# Clock_management.net
KiCad netlist of a schematic drawn in Altium Designer
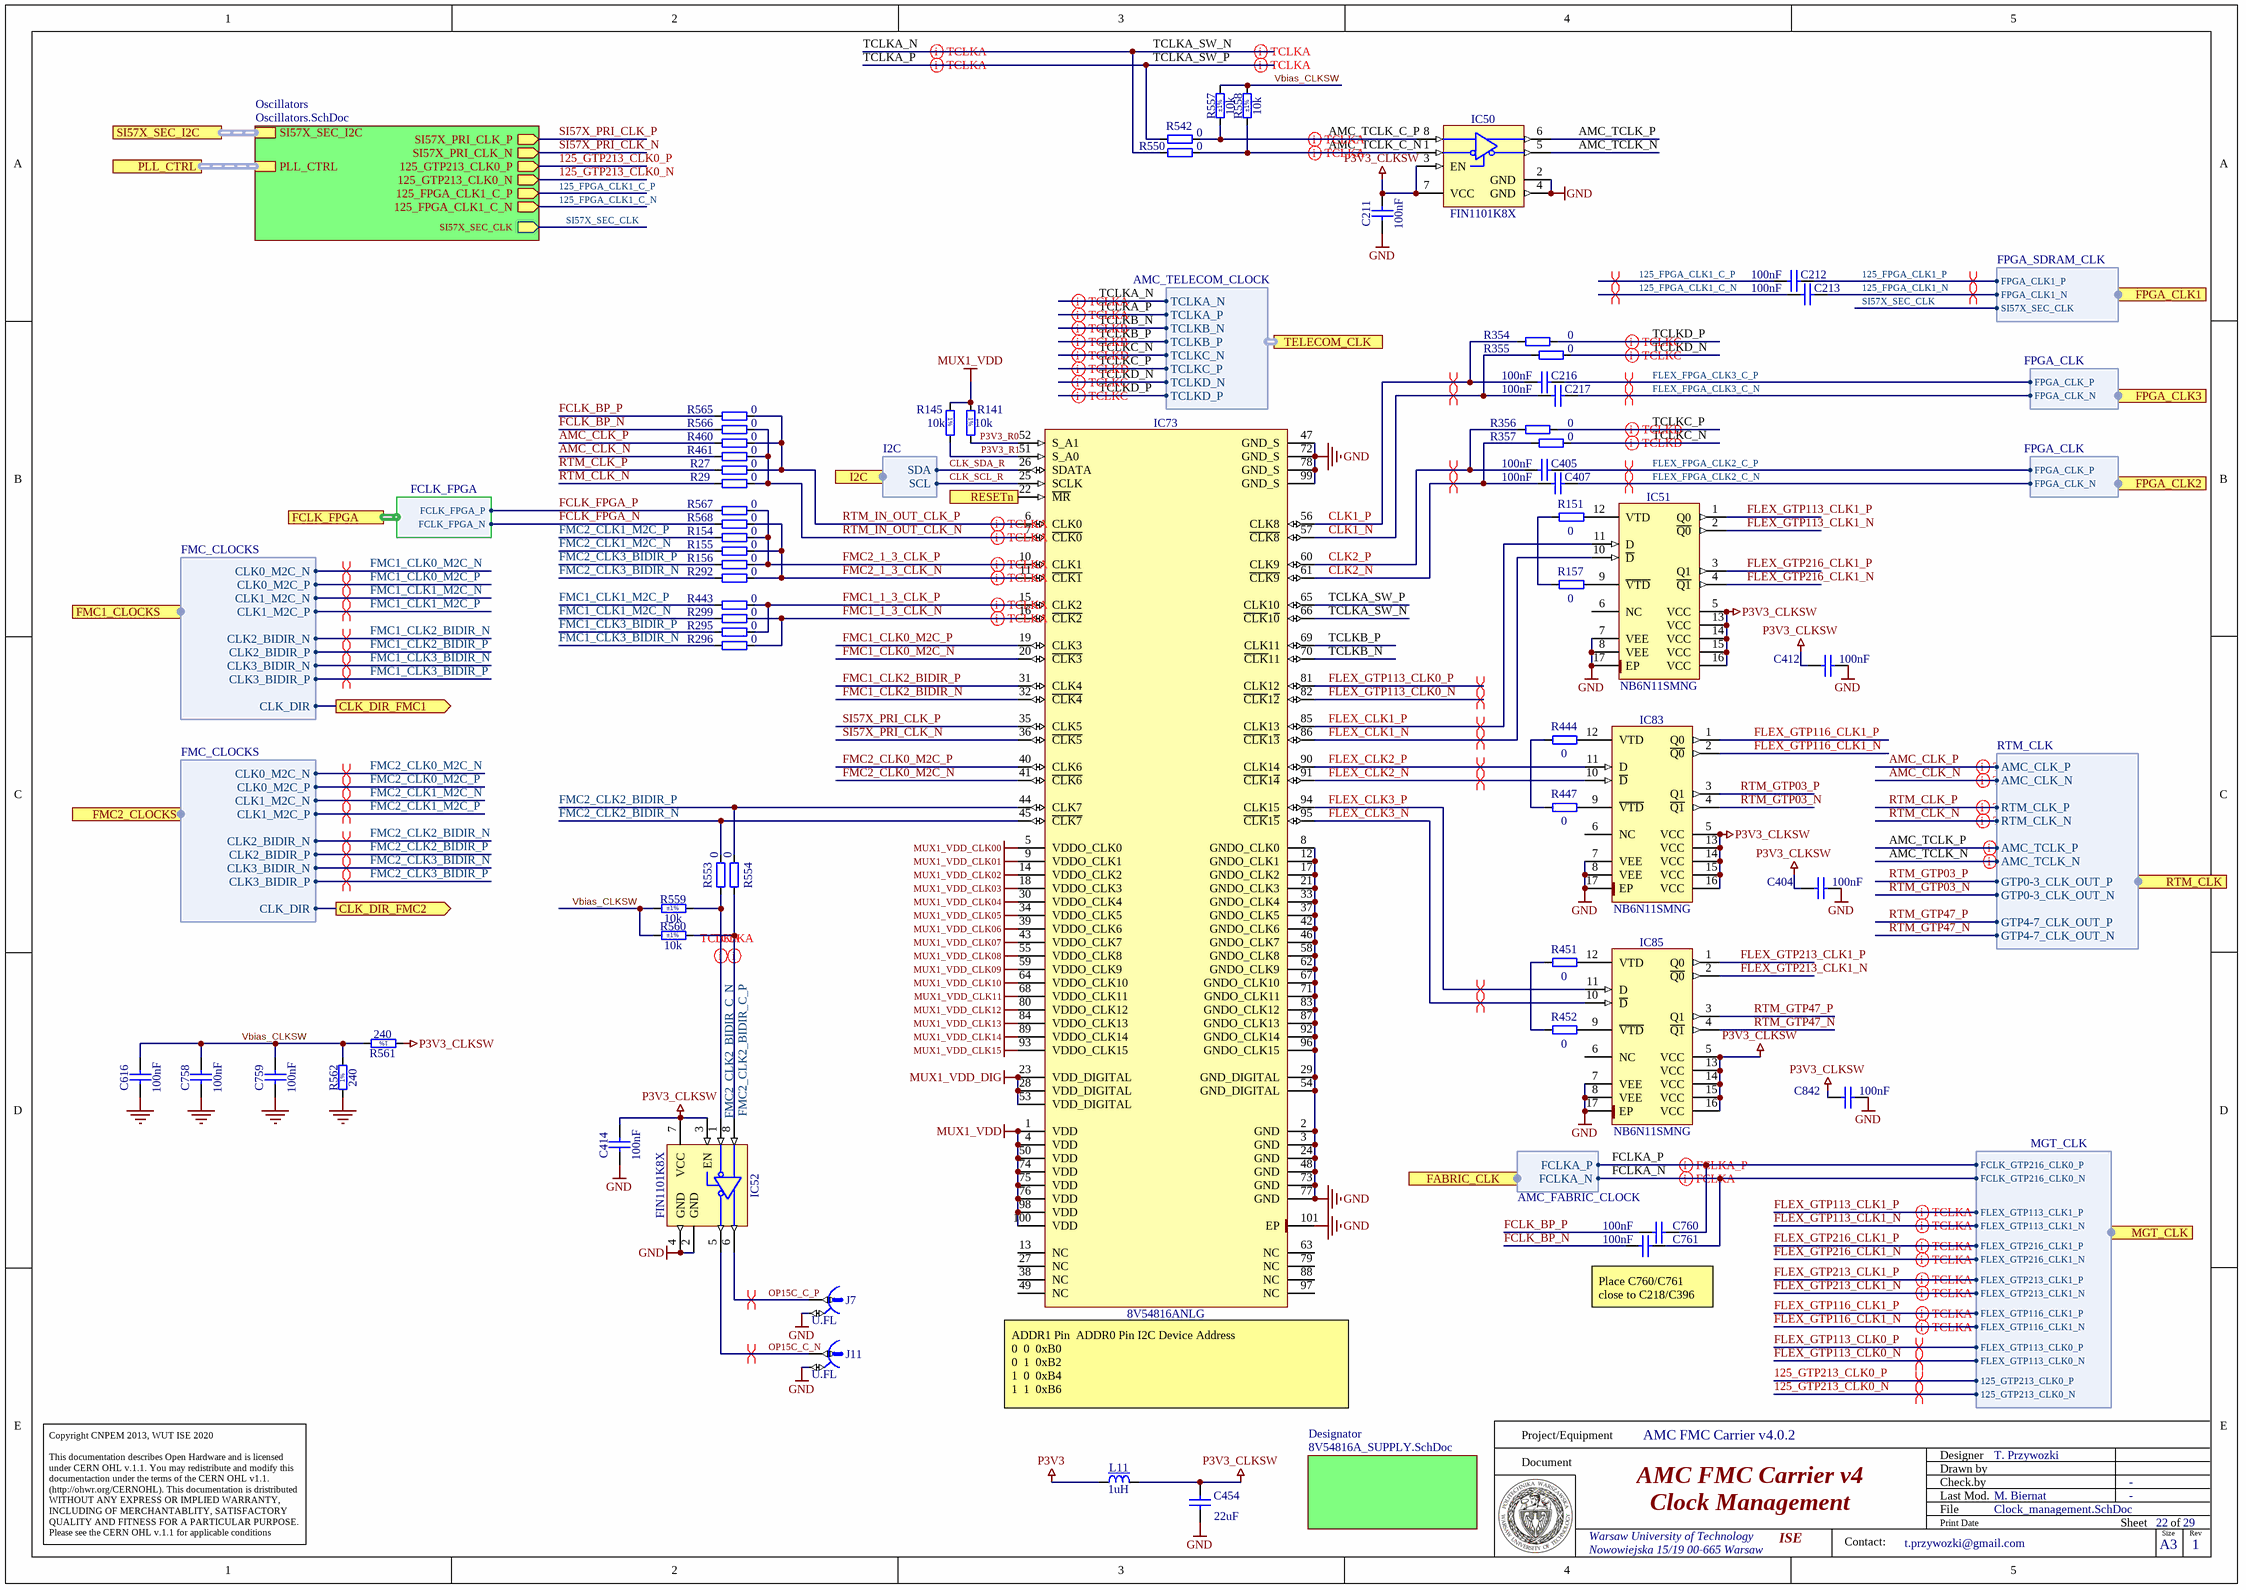
[diagram p0: Clock_management.SchDoc]

(export (version "E")
  (design (tool "Eeschema 10.0.6"))
  (components
    (comp (ref "C211")
      (value "100nF")
      (footprint "CAPC1005X55N")
      (description "Non-polarised capacitor")
      (fields
        (field (name "MANUFACTURER PART NUMBER") "CC0402_100NF_16V_10%_X5R")
        (field (name "MANUFACTURER") "GENERIC")
        (field (name "AUTHOR") "CERN DEM JLC")
      )
      (libsource (lib "Capacitors") (part "Capacitor - non polarized"))
    )
    (comp (ref "C212")
      (value "100nF")
      (footprint "CAPC0603X33N")
      (description "Non-polarised capacitor")
      (fields
        (field (name "PART NUMBER") "CC0201_100NF_6.3V_10%_X5R")
        (field (name "VOLTAGE") "6.3V")
        (field (name "AUTHOR") "CERN DEM JLC")
      )
      (libsource (lib "Capacitors") (part "Capacitor - non polarized"))
    )
    (comp (ref "C213")
      (value "100nF")
      (footprint "CAPC0603X33N")
      (description "Non-polarised capacitor")
      (fields
        (field (name "PART NUMBER") "CC0201_100NF_6.3V_10%_X5R")
        (field (name "VOLTAGE") "6.3V")
        (field (name "AUTHOR") "CERN DEM JLC")
      )
      (libsource (lib "Capacitors") (part "Capacitor - non polarized"))
    )
    (comp (ref "C216")
      (value "100nF")
      (footprint "CAPC0603X33N")
      (description "Non-polarised capacitor")
      (fields
        (field (name "PART NUMBER") "CC0201_100NF_6.3V_10%_X5R")
        (field (name "VOLTAGE") "6.3V")
        (field (name "AUTHOR") "CERN DEM JLC")
      )
      (libsource (lib "Capacitors") (part "Capacitor - non polarized"))
    )
    (comp (ref "C217")
      (value "100nF")
      (footprint "CAPC0603X33N")
      (description "Non-polarised capacitor")
      (fields
        (field (name "PART NUMBER") "CC0201_100NF_6.3V_10%_X5R")
        (field (name "VOLTAGE") "6.3V")
        (field (name "AUTHOR") "CERN DEM JLC")
      )
      (libsource (lib "Capacitors") (part "Capacitor - non polarized"))
    )
    (comp (ref "C404")
      (value "100nF")
      (footprint "CAPC0603X33N")
      (description "Non-polarised capacitor")
      (fields
        (field (name "PART NUMBER") "CC0201_100NF_6.3V_10%_X5R")
        (field (name "VOLTAGE") "6.3V")
        (field (name "AUTHOR") "CERN DEM JLC")
      )
      (libsource (lib "Capacitors") (part "Capacitor - non polarized"))
    )
    (comp (ref "C405")
      (value "100nF")
      (footprint "CAPC0603X33N")
      (description "Non-polarised capacitor")
      (fields
        (field (name "PART NUMBER") "CC0201_100NF_6.3V_10%_X5R")
        (field (name "VOLTAGE") "6.3V")
        (field (name "AUTHOR") "CERN DEM JLC")
      )
      (libsource (lib "Capacitors") (part "Capacitor - non polarized"))
    )
    (comp (ref "C407")
      (value "100nF")
      (footprint "CAPC0603X33N")
      (description "Non-polarised capacitor")
      (fields
        (field (name "PART NUMBER") "CC0201_100NF_6.3V_10%_X5R")
        (field (name "VOLTAGE") "6.3V")
        (field (name "AUTHOR") "CERN DEM JLC")
      )
      (libsource (lib "Capacitors") (part "Capacitor - non polarized"))
    )
    (comp (ref "C412")
      (value "100nF")
      (footprint "CAPC0603X33N")
      (description "Non-polarised capacitor")
      (fields
        (field (name "PART NUMBER") "CC0201_100NF_6.3V_10%_X5R")
        (field (name "VOLTAGE") "6.3V")
        (field (name "AUTHOR") "CERN DEM JLC")
      )
      (libsource (lib "Capacitors") (part "Capacitor - non polarized"))
    )
    (comp (ref "C414")
      (value "100nF")
      (footprint "CAPC1005X55N")
      (description "Non-polarised capacitor")
      (fields
        (field (name "MANUFACTURER PART NUMBER") "CC0402_100NF_16V_10%_X5R")
        (field (name "MANUFACTURER") "GENERIC")
        (field (name "AUTHOR") "CERN DEM JLC")
      )
      (libsource (lib "Capacitors") (part "Capacitor - non polarized"))
    )
    (comp (ref "C454")
      (value "22uF")
      (footprint "CAPC3216X180N")
      (description "Non-polarised capacitor")
      (fields
        (field (name "PART NUMBER") "CC1206_22UF_10V_10%_X7R")
        (field (name "VOLTAGE") "10V")
        (field (name "AUTHOR") "CERN DEM JLC")
      )
      (libsource (lib "Capacitors") (part "Capacitor - non polarized"))
    )
    (comp (ref "C616")
      (value "100nF")
      (footprint "CAPC1005X55N")
      (description "Non-polarised capacitor")
      (fields
        (field (name "MANUFACTURER PART NUMBER") "CC0402_100NF_16V_10%_X5R")
        (field (name "MANUFACTURER") "GENERIC")
        (field (name "AUTHOR") "CERN DEM JLC")
      )
      (libsource (lib "Capacitors") (part "Capacitor - non polarized"))
    )
    (comp (ref "C758")
      (value "100nF")
      (footprint "CAPC1005X55N")
      (description "Non-polarised capacitor")
      (fields
        (field (name "MANUFACTURER PART NUMBER") "CC0402_100NF_16V_10%_X5R")
        (field (name "MANUFACTURER") "GENERIC")
        (field (name "AUTHOR") "CERN DEM JLC")
      )
      (libsource (lib "Capacitors") (part "Capacitor - non polarized"))
    )
    (comp (ref "C759")
      (value "100nF")
      (footprint "CAPC1005X55N")
      (description "Non-polarised capacitor")
      (fields
        (field (name "MANUFACTURER PART NUMBER") "CC0402_100NF_16V_10%_X5R")
        (field (name "MANUFACTURER") "GENERIC")
        (field (name "AUTHOR") "CERN DEM JLC")
      )
      (libsource (lib "Capacitors") (part "Capacitor - non polarized"))
    )
    (comp (ref "C760")
      (value "100nF")
      (footprint "CAPC0603X33N")
      (description "Non-polarised capacitor")
      (fields
        (field (name "PART NUMBER") "CC0201_100NF_6.3V_10%_X5R")
        (field (name "VOLTAGE") "6.3V")
        (field (name "AUTHOR") "CERN DEM JLC")
      )
      (libsource (lib "Capacitors") (part "Capacitor - non polarized"))
    )
    (comp (ref "C761")
      (value "100nF")
      (footprint "CAPC0603X33N")
      (description "Non-polarised capacitor")
      (fields
        (field (name "PART NUMBER") "CC0201_100NF_6.3V_10%_X5R")
        (field (name "VOLTAGE") "6.3V")
        (field (name "AUTHOR") "CERN DEM JLC")
      )
      (libsource (lib "Capacitors") (part "Capacitor - non polarized"))
    )
    (comp (ref "C842")
      (value "100nF")
      (footprint "CAPC0603X33N")
      (description "Non-polarised capacitor")
      (fields
        (field (name "PART NUMBER") "CC0201_100NF_6.3V_10%_X5R")
        (field (name "VOLTAGE") "6.3V")
        (field (name "AUTHOR") "CERN DEM JLC")
      )
      (libsource (lib "Capacitors") (part "Capacitor - non polarized"))
    )
    (comp (ref "IC50")
      (value "FIN1101K8X")
      (footprint "SOP50P310X90-8N")
      (description "LVDS Single Port High Speed Repeater")
      (fields (field (name "MANUFACTURER") "FAIRCHILD SEMICONDUCTOR") (field (name "AUTHOR") "CERN DEM JLC"))
      (libsource (lib "") (part "FIN1101K8X_1"))
    )
    (comp (ref "IC51")
      (value "NB6N11SMNG")
      (footprint "QFN50P300X300X100-17N-S185")
      (description "3.3V 1:2 AnyLevel Input to LVDS Fanout Buffer / Translator")
      (fields (field (name "MANUFACTURER") "ON SEMICONDUCTOR") (field (name "AUTHOR") "CERN DEM JLC"))
      (libsource (lib "ICs And Semiconductors") (part "NB6N11SMN"))
    )
    (comp (ref "IC52")
      (value "FIN1101K8X")
      (footprint "SOP50P310X90-8N")
      (description "LVDS Single Port High Speed Repeater")
      (fields (field (name "MANUFACTURER") "FAIRCHILD SEMICONDUCTOR") (field (name "AUTHOR") "CERN DEM JLC"))
      (libsource (lib "ICs And Semiconductors") (part "FIN1101K8X"))
    )
    (comp (ref "IC73")
      (value "8V54816ANLG")
      (footprint "QFN40P1200X1200X90-101N-S690")
      (description "16-Port, Bi-directional M-LVDS Clock Cross-Point Switch")
      (fields
        (field (name "MANUFACTURER") "INTEGRATED DEVICE TECHNOLOGY (IDT)")
        (field (name "AUTHOR") "CERN DEM MR")
      )
      (libsource (lib "ICs And Semiconductors") (part "8V54816ANLG"))
    )
    (comp (ref "IC83")
      (value "NB6N11SMNG")
      (footprint "QFN50P300X300X100-17N-S185")
      (description "3.3V 1:2 AnyLevel Input to LVDS Fanout Buffer / Translator")
      (fields (field (name "MANUFACTURER") "ON SEMICONDUCTOR") (field (name "AUTHOR") "CERN DEM JLC"))
      (libsource (lib "ICs And Semiconductors") (part "NB6N11SMN"))
    )
    (comp (ref "IC85")
      (value "NB6N11SMNG")
      (footprint "QFN50P300X300X100-17N-S185")
      (description "3.3V 1:2 AnyLevel Input to LVDS Fanout Buffer / Translator")
      (fields (field (name "MANUFACTURER") "ON SEMICONDUCTOR") (field (name "AUTHOR") "CERN DEM JLC"))
      (libsource (lib "ICs And Semiconductors") (part "NB6N11SMN"))
    )
    (comp (ref "J7")
      (value "U.FL")
      (footprint "HIROSE_U.FL-R-SMT-1(10)")
      (fields
        (field (name "PART NUMBER") "HIROSE_U.FL-R-SMT-1(10)")
        (field (name "MANUFACTURER") "HIROSE (HRS)")
        (field (name "MANUFACTURER PART NUMBER") "U.FL-R-SMT-1(10)")
        (field (name "AUTHOR") "CERN DEM JLC")
      )
      (libsource (lib "Connectors") (part "Coax_1Male_1Shield"))
    )
    (comp (ref "J11")
      (value "U.FL")
      (footprint "HIROSE_U.FL-R-SMT-1(10)")
      (fields
        (field (name "PART NUMBER") "HIROSE_U.FL-R-SMT-1(10)")
        (field (name "MANUFACTURER") "HIROSE (HRS)")
        (field (name "MANUFACTURER PART NUMBER") "U.FL-R-SMT-1(10)")
        (field (name "AUTHOR") "CERN DEM JLC")
      )
      (libsource (lib "Connectors") (part "Coax_1Male_1Shield"))
    )
    (comp (ref "L11")
      (value "1uH")
      (footprint "IND_PANASONIC_ELLVGG")
      (description "Inductor With Core")
      (fields
        (field (name "PART NUMBER") "IND_1UH_30%_PANASONIC_ELLVGG1R0N")
        (field (name "POWER") "1.8A")
        (field (name "AUTHOR") "CERN DEM JLC")
      )
      (libsource (lib "Inductors & Transformers") (part "Inductor With Magnetic core"))
    )
    (comp (ref "R27")
      (value "0")
      (footprint "RESC1005X40N")
      (description "Resistor")
      (fields
        (field (name "PART NUMBER") "R0402_0R_JUMPER")
        (field (name "MANUFACTURER") "GENERIC")
        (field (name "AUTHOR") "CERN DEM JLC")
      )
      (libsource (lib "Resistors") (part "Resistor"))
    )
    (comp (ref "R29")
      (value "0")
      (footprint "RESC1005X40N")
      (description "Resistor")
      (fields
        (field (name "PART NUMBER") "R0402_0R_JUMPER")
        (field (name "MANUFACTURER") "GENERIC")
        (field (name "AUTHOR") "CERN DEM JLC")
      )
      (libsource (lib "Resistors") (part "Resistor"))
    )
    (comp (ref "R141")
      (value "10k")
      (footprint "RESC1005X40N")
      (description "Resistor - 1%")
      (fields
        (field (name "PART NUMBER") "R0402_10K_1%_0.0625W_100PPM")
        (field (name "POWER") "0.0625W")
        (field (name "AUTHOR") "CERN DEM JLC")
      )
      (libsource (lib "Resistors") (part "Resistor - 1%"))
    )
    (comp (ref "R145")
      (value "10k")
      (footprint "RESC1005X40N")
      (description "Resistor - 1%")
      (fields
        (field (name "PART NUMBER") "R0402_10K_1%_0.0625W_100PPM")
        (field (name "POWER") "0.0625W")
        (field (name "AUTHOR") "CERN DEM JLC")
      )
      (libsource (lib "Resistors") (part "Resistor - 1%"))
    )
    (comp (ref "R151")
      (value "0")
      (footprint "RESC1005X40N")
      (description "Resistor")
      (fields
        (field (name "PART NUMBER") "R0402_0R_JUMPER")
        (field (name "MANUFACTURER") "GENERIC")
        (field (name "AUTHOR") "CERN DEM JLC")
      )
      (libsource (lib "Resistors") (part "Resistor"))
    )
    (comp (ref "R154")
      (value "0")
      (footprint "RESC1005X40N")
      (description "Resistor")
      (fields
        (field (name "PART NUMBER") "R0402_0R_JUMPER")
        (field (name "MANUFACTURER") "GENERIC")
        (field (name "AUTHOR") "CERN DEM JLC")
      )
      (libsource (lib "Resistors") (part "Resistor"))
    )
    (comp (ref "R155")
      (value "0")
      (footprint "RESC1005X40N")
      (description "Resistor")
      (fields
        (field (name "PART NUMBER") "R0402_0R_JUMPER")
        (field (name "MANUFACTURER") "GENERIC")
        (field (name "AUTHOR") "CERN DEM JLC")
      )
      (libsource (lib "Resistors") (part "Resistor"))
    )
    (comp (ref "R156")
      (value "0")
      (footprint "RESC1005X40N")
      (description "Resistor")
      (fields
        (field (name "PART NUMBER") "R0402_0R_JUMPER")
        (field (name "MANUFACTURER") "GENERIC")
        (field (name "AUTHOR") "CERN DEM JLC")
      )
      (libsource (lib "Resistors") (part "Resistor"))
    )
    (comp (ref "R157")
      (value "0")
      (footprint "RESC1005X40N")
      (description "Resistor")
      (fields
        (field (name "PART NUMBER") "R0402_0R_JUMPER")
        (field (name "MANUFACTURER") "GENERIC")
        (field (name "AUTHOR") "CERN DEM JLC")
      )
      (libsource (lib "Resistors") (part "Resistor"))
    )
    (comp (ref "R292")
      (value "0")
      (footprint "RESC1005X40N")
      (description "Resistor")
      (fields
        (field (name "PART NUMBER") "R0402_0R_JUMPER")
        (field (name "MANUFACTURER") "GENERIC")
        (field (name "AUTHOR") "CERN DEM JLC")
      )
      (libsource (lib "Resistors") (part "Resistor"))
    )
    (comp (ref "R295")
      (value "0")
      (footprint "RESC1005X40N")
      (description "Resistor")
      (fields
        (field (name "PART NUMBER") "R0402_0R_JUMPER")
        (field (name "MANUFACTURER") "GENERIC")
        (field (name "AUTHOR") "CERN DEM JLC")
      )
      (libsource (lib "Resistors") (part "Resistor"))
    )
    (comp (ref "R296")
      (value "0")
      (footprint "RESC1005X40N")
      (description "Resistor")
      (fields
        (field (name "PART NUMBER") "R0402_0R_JUMPER")
        (field (name "MANUFACTURER") "GENERIC")
        (field (name "AUTHOR") "CERN DEM JLC")
      )
      (libsource (lib "Resistors") (part "Resistor"))
    )
    (comp (ref "R299")
      (value "0")
      (footprint "RESC1005X40N")
      (description "Resistor")
      (fields
        (field (name "PART NUMBER") "R0402_0R_JUMPER")
        (field (name "MANUFACTURER") "GENERIC")
        (field (name "AUTHOR") "CERN DEM JLC")
      )
      (libsource (lib "Resistors") (part "Resistor"))
    )
    (comp (ref "R354")
      (value "0")
      (footprint "RESC0603X28N")
      (description "Resistor")
      (fields
        (field (name "PART NUMBER") "R0201_0R_JUMPER")
        (field (name "MANUFACTURER") "GENERIC")
        (field (name "AUTHOR") "CERN DEM JLC")
      )
      (libsource (lib "Resistors") (part "Resistor"))
    )
    (comp (ref "R355")
      (value "0")
      (footprint "RESC0603X28N")
      (description "Resistor")
      (fields
        (field (name "PART NUMBER") "R0201_0R_JUMPER")
        (field (name "MANUFACTURER") "GENERIC")
        (field (name "AUTHOR") "CERN DEM JLC")
      )
      (libsource (lib "Resistors") (part "Resistor"))
    )
    (comp (ref "R356")
      (value "0")
      (footprint "RESC0603X28N")
      (description "Resistor")
      (fields
        (field (name "PART NUMBER") "R0201_0R_JUMPER")
        (field (name "MANUFACTURER") "GENERIC")
        (field (name "AUTHOR") "CERN DEM JLC")
      )
      (libsource (lib "Resistors") (part "Resistor"))
    )
    (comp (ref "R357")
      (value "0")
      (footprint "RESC0603X28N")
      (description "Resistor")
      (fields
        (field (name "PART NUMBER") "R0201_0R_JUMPER")
        (field (name "MANUFACTURER") "GENERIC")
        (field (name "AUTHOR") "CERN DEM JLC")
      )
      (libsource (lib "Resistors") (part "Resistor"))
    )
    (comp (ref "R443")
      (value "0")
      (footprint "RESC1005X40N")
      (description "Resistor")
      (fields
        (field (name "PART NUMBER") "R0402_0R_JUMPER")
        (field (name "MANUFACTURER") "GENERIC")
        (field (name "AUTHOR") "CERN DEM JLC")
      )
      (libsource (lib "Resistors") (part "Resistor"))
    )
    (comp (ref "R444")
      (value "0")
      (footprint "RESC1005X40N")
      (description "Resistor")
      (fields
        (field (name "PART NUMBER") "R0402_0R_JUMPER")
        (field (name "MANUFACTURER") "GENERIC")
        (field (name "AUTHOR") "CERN DEM JLC")
      )
      (libsource (lib "Resistors") (part "Resistor"))
    )
    (comp (ref "R447")
      (value "0")
      (footprint "RESC1005X40N")
      (description "Resistor")
      (fields
        (field (name "PART NUMBER") "R0402_0R_JUMPER")
        (field (name "MANUFACTURER") "GENERIC")
        (field (name "AUTHOR") "CERN DEM JLC")
      )
      (libsource (lib "Resistors") (part "Resistor"))
    )
    (comp (ref "R451")
      (value "0")
      (footprint "RESC1005X40N")
      (description "Resistor")
      (fields
        (field (name "PART NUMBER") "R0402_0R_JUMPER")
        (field (name "MANUFACTURER") "GENERIC")
        (field (name "AUTHOR") "CERN DEM JLC")
      )
      (libsource (lib "Resistors") (part "Resistor"))
    )
    (comp (ref "R452")
      (value "0")
      (footprint "RESC1005X40N")
      (description "Resistor")
      (fields
        (field (name "PART NUMBER") "R0402_0R_JUMPER")
        (field (name "MANUFACTURER") "GENERIC")
        (field (name "AUTHOR") "CERN DEM JLC")
      )
      (libsource (lib "Resistors") (part "Resistor"))
    )
    (comp (ref "R460")
      (value "0")
      (footprint "RESC1005X40N")
      (description "Resistor")
      (fields
        (field (name "PART NUMBER") "R0402_0R_JUMPER")
        (field (name "MANUFACTURER") "GENERIC")
        (field (name "AUTHOR") "CERN DEM JLC")
      )
      (libsource (lib "Resistors") (part "Resistor"))
    )
    (comp (ref "R461")
      (value "0")
      (footprint "RESC1005X40N")
      (description "Resistor")
      (fields
        (field (name "PART NUMBER") "R0402_0R_JUMPER")
        (field (name "MANUFACTURER") "GENERIC")
        (field (name "AUTHOR") "CERN DEM JLC")
      )
      (libsource (lib "Resistors") (part "Resistor"))
    )
    (comp (ref "R542")
      (value "0")
      (footprint "RESC1005X40N")
      (description "Resistor")
      (fields
        (field (name "PART NUMBER") "R0402_0R_JUMPER")
        (field (name "MANUFACTURER") "GENERIC")
        (field (name "AUTHOR") "CERN DEM JLC")
      )
      (libsource (lib "Resistors") (part "Resistor"))
    )
    (comp (ref "R550")
      (value "0")
      (footprint "RESC1005X40N")
      (description "Resistor")
      (fields
        (field (name "PART NUMBER") "R0402_0R_JUMPER")
        (field (name "MANUFACTURER") "GENERIC")
        (field (name "AUTHOR") "CERN DEM JLC")
      )
      (libsource (lib "Resistors") (part "Resistor"))
    )
    (comp (ref "R553")
      (value "0")
      (footprint "RESC1005X40N")
      (description "Resistor")
      (fields
        (field (name "PART NUMBER") "R0402_0R_JUMPER")
        (field (name "MANUFACTURER") "GENERIC")
        (field (name "AUTHOR") "CERN DEM JLC")
      )
      (libsource (lib "Resistors") (part "Resistor"))
    )
    (comp (ref "R554")
      (value "0")
      (footprint "RESC1005X40N")
      (description "Resistor")
      (fields
        (field (name "PART NUMBER") "R0402_0R_JUMPER")
        (field (name "MANUFACTURER") "GENERIC")
        (field (name "AUTHOR") "CERN DEM JLC")
      )
      (libsource (lib "Resistors") (part "Resistor"))
    )
    (comp (ref "R557")
      (value "10k")
      (footprint "RESC1005X40N")
      (description "Resistor - 1%")
      (fields
        (field (name "TOLERANCE") "±1%")
        (field (name "PART NUMBER") "R0402_10K_1%_0.0625W_100PPM")
        (field (name "POWER") "0.0625W")
        (field (name "AUTHOR") "CERN DEM JLC")
      )
      (libsource (lib "Resistors") (part "Resistor - 1%"))
    )
    (comp (ref "R558")
      (value "10k")
      (footprint "RESC1005X40N")
      (description "Resistor - 1%")
      (fields
        (field (name "TOLERANCE") "±1%")
        (field (name "PART NUMBER") "R0402_10K_1%_0.0625W_100PPM")
        (field (name "POWER") "0.0625W")
        (field (name "AUTHOR") "CERN DEM JLC")
      )
      (libsource (lib "Resistors") (part "Resistor - 1%"))
    )
    (comp (ref "R559")
      (value "10k")
      (footprint "RESC1005X40N")
      (description "Resistor - 1%")
      (fields
        (field (name "TOLERANCE") "±1%")
        (field (name "PART NUMBER") "R0402_10K_1%_0.0625W_100PPM")
        (field (name "POWER") "0.0625W")
        (field (name "AUTHOR") "CERN DEM JLC")
      )
      (libsource (lib "Resistors") (part "Resistor - 1%"))
    )
    (comp (ref "R560")
      (value "10k")
      (footprint "RESC1005X40N")
      (description "Resistor - 1%")
      (fields
        (field (name "TOLERANCE") "±1%")
        (field (name "PART NUMBER") "R0402_10K_1%_0.0625W_100PPM")
        (field (name "POWER") "0.0625W")
        (field (name "AUTHOR") "CERN DEM JLC")
      )
      (libsource (lib "Resistors") (part "Resistor - 1%"))
    )
    (comp (ref "R561")
      (value "240")
      (footprint "RESC1005X40N")
      (description "Resistor - 1%")
      (fields
        (field (name "MANUFACTURER PART NUMBER") "R0402_240R_1%_0.0625W_100PPM")
        (field (name "MANUFACTURER") "GENERIC")
        (field (name "AUTHOR") "CERN DEM JLC")
      )
      (libsource (lib "Resistors") (part "Resistor - 1%"))
    )
    (comp (ref "R562")
      (value "240")
      (footprint "RESC1005X40N")
      (description "Resistor - 1%")
      (fields
        (field (name "MANUFACTURER PART NUMBER") "R0402_240R_1%_0.0625W_100PPM")
        (field (name "MANUFACTURER") "GENERIC")
        (field (name "AUTHOR") "CERN DEM JLC")
      )
      (libsource (lib "Resistors") (part "Resistor - 1%"))
    )
    (comp (ref "R565")
      (value "0")
      (footprint "RESC1005X40N")
      (description "Resistor")
      (fields
        (field (name "PART NUMBER") "R0402_0R_JUMPER")
        (field (name "MANUFACTURER") "GENERIC")
        (field (name "AUTHOR") "CERN DEM JLC")
      )
      (libsource (lib "Resistors") (part "Resistor"))
    )
    (comp (ref "R566")
      (value "0")
      (footprint "RESC1005X40N")
      (description "Resistor")
      (fields
        (field (name "PART NUMBER") "R0402_0R_JUMPER")
        (field (name "MANUFACTURER") "GENERIC")
        (field (name "AUTHOR") "CERN DEM JLC")
      )
      (libsource (lib "Resistors") (part "Resistor"))
    )
    (comp (ref "R567")
      (value "0")
      (footprint "RESC1005X40N")
      (description "Resistor")
      (fields
        (field (name "PART NUMBER") "R0402_0R_JUMPER")
        (field (name "MANUFACTURER") "GENERIC")
        (field (name "AUTHOR") "CERN DEM JLC")
      )
      (libsource (lib "Resistors") (part "Resistor"))
    )
    (comp (ref "R568")
      (value "0")
      (footprint "RESC1005X40N")
      (description "Resistor")
      (fields
        (field (name "PART NUMBER") "R0402_0R_JUMPER")
        (field (name "MANUFACTURER") "GENERIC")
        (field (name "AUTHOR") "CERN DEM JLC")
      )
      (libsource (lib "Resistors") (part "Resistor"))
    )
  )
  (nets
    (net (code "12") (name "/125_FPGA_CLK1_C_N") (class "Default")
      (node (ref "C213") (pin "1") (pinfunction "1_1") (pintype "passive"))
    )
    (net (code "13") (name "/125_FPGA_CLK1_C_P") (class "Default")
      (node (ref "C212") (pin "1") (pinfunction "1_1") (pintype "passive"))
    )
    (net (code "14") (name "/125_FPGA_CLK1_N") (class "Default")
      (node (ref "C213") (pin "2") (pinfunction "2_2") (pintype "passive"))
    )
    (net (code "15") (name "/125_FPGA_CLK1_P") (class "Default")
      (node (ref "C212") (pin "2") (pinfunction "2_2") (pintype "passive"))
    )
    (net (code "18") (name "/AMC_CLK_N") (class "Default")
      (node (ref "R461") (pin "1") (pinfunction "1_1") (pintype "passive"))
    )
    (net (code "19") (name "/AMC_CLK_P") (class "Default")
      (node (ref "R460") (pin "1") (pinfunction "1_1") (pintype "passive"))
    )
    (net (code "20") (name "/AMC_TCLK_C_N") (class "Default")
      (node (ref "IC50") (pin "1") (pinfunction "RIN-_1") (pintype "input"))
      (node (ref "R550") (pin "2") (pinfunction "2_2") (pintype "passive"))
      (node (ref "R558") (pin "1") (pinfunction "1_1") (pintype "passive"))
    )
    (net (code "21") (name "/AMC_TCLK_C_P") (class "Default")
      (node (ref "IC50") (pin "8") (pinfunction "RIN+_8") (pintype "input"))
      (node (ref "R542") (pin "2") (pinfunction "2_2") (pintype "passive"))
      (node (ref "R557") (pin "1") (pinfunction "1_1") (pintype "passive"))
    )
    (net (code "22") (name "/AMC_TCLK_N") (class "Default")
      (node (ref "IC50") (pin "5") (pinfunction "DOUT-_5") (pintype "output"))
    )
    (net (code "23") (name "/AMC_TCLK_P") (class "Default")
      (node (ref "IC50") (pin "6") (pinfunction "DOUT+_6") (pintype "output"))
    )
    (net (code "24") (name "/CLK1_N") (class "Default")
      (node (ref "C217") (pin "1") (pinfunction "1_1") (pintype "passive"))
      (node (ref "IC73") (pin "57") (pinfunction "~{CLK8}_57") (pintype "bidirectional"))
      (node (ref "R355") (pin "1") (pinfunction "1_1") (pintype "passive"))
    )
    (net (code "25") (name "/CLK1_P") (class "Default")
      (node (ref "C216") (pin "1") (pinfunction "1_1") (pintype "passive"))
      (node (ref "IC73") (pin "56") (pinfunction "CLK8_56") (pintype "bidirectional"))
      (node (ref "R354") (pin "1") (pinfunction "1_1") (pintype "passive"))
    )
    (net (code "26") (name "/CLK2_N") (class "Default")
      (node (ref "C407") (pin "1") (pinfunction "1_1") (pintype "passive"))
      (node (ref "IC73") (pin "61") (pinfunction "~{CLK9}_61") (pintype "bidirectional"))
      (node (ref "R357") (pin "1") (pinfunction "1_1") (pintype "passive"))
    )
    (net (code "27") (name "/CLK2_P") (class "Default")
      (node (ref "C405") (pin "1") (pinfunction "1_1") (pintype "passive"))
      (node (ref "IC73") (pin "60") (pinfunction "CLK9_60") (pintype "bidirectional"))
      (node (ref "R356") (pin "1") (pinfunction "1_1") (pintype "passive"))
    )
    (net (code "30") (name "/CLK_SCL_R") (class "Default")
      (node (ref "IC73") (pin "25") (pinfunction "SCLK_25") (pintype "input"))
    )
    (net (code "31") (name "/CLK_SDA_R") (class "Default")
      (node (ref "IC73") (pin "26") (pinfunction "SDATA_26") (pintype "bidirectional"))
    )
    (net (code "32") (name "/FCLKA_N") (class "Default")
      (node (ref "C761") (pin "2") (pinfunction "2_2") (pintype "passive"))
    )
    (net (code "33") (name "/FCLKA_P") (class "Default")
      (node (ref "C760") (pin "2") (pinfunction "2_2") (pintype "passive"))
    )
    (net (code "34") (name "/FCLK_BP_N") (class "Default")
      (node (ref "C761") (pin "1") (pinfunction "1_1") (pintype "passive"))
      (node (ref "R566") (pin "1") (pinfunction "1_1") (pintype "passive"))
    )
    (net (code "35") (name "/FCLK_BP_P") (class "Default")
      (node (ref "C760") (pin "1") (pinfunction "1_1") (pintype "passive"))
      (node (ref "R565") (pin "1") (pinfunction "1_1") (pintype "passive"))
    )
    (net (code "36") (name "/FCLK_FPGA_N") (class "Default")
      (node (ref "R568") (pin "1") (pinfunction "1_1") (pintype "passive"))
    )
    (net (code "37") (name "/FCLK_FPGA_P") (class "Default")
      (node (ref "R567") (pin "1") (pinfunction "1_1") (pintype "passive"))
    )
    (net (code "38") (name "/FLEX_CLK1_N") (class "Default")
      (node (ref "IC51") (pin "10") (pinfunction "~{D}_10") (pintype "input"))
      (node (ref "IC73") (pin "86") (pinfunction "~{CLK}1~{3}_86") (pintype "bidirectional"))
    )
    (net (code "39") (name "/FLEX_CLK1_P") (class "Default")
      (node (ref "IC51") (pin "11") (pinfunction "D_11") (pintype "input"))
      (node (ref "IC73") (pin "85") (pinfunction "CLK13_85") (pintype "bidirectional"))
    )
    (net (code "40") (name "/FLEX_CLK2_N") (class "Default")
      (node (ref "IC73") (pin "91") (pinfunction "~{CLK}1~{4}_91") (pintype "bidirectional"))
      (node (ref "IC83") (pin "10") (pinfunction "~{D}_10") (pintype "input"))
    )
    (net (code "41") (name "/FLEX_CLK2_P") (class "Default")
      (node (ref "IC73") (pin "90") (pinfunction "CLK14_90") (pintype "bidirectional"))
      (node (ref "IC83") (pin "11") (pinfunction "D_11") (pintype "input"))
    )
    (net (code "42") (name "/FLEX_CLK3_N") (class "Default")
      (node (ref "IC73") (pin "95") (pinfunction "~{CLK}1~{5}_95") (pintype "bidirectional"))
      (node (ref "IC85") (pin "10") (pinfunction "~{D}_10") (pintype "input"))
    )
    (net (code "43") (name "/FLEX_CLK3_P") (class "Default")
      (node (ref "IC73") (pin "94") (pinfunction "CLK15_94") (pintype "bidirectional"))
      (node (ref "IC85") (pin "11") (pinfunction "D_11") (pintype "input"))
    )
    (net (code "44") (name "/FLEX_FPGA_CLK2_C_N") (class "Default")
      (node (ref "C407") (pin "2") (pinfunction "2_2") (pintype "passive"))
    )
    (net (code "45") (name "/FLEX_FPGA_CLK2_C_P") (class "Default")
      (node (ref "C405") (pin "2") (pinfunction "2_2") (pintype "passive"))
    )
    (net (code "46") (name "/FLEX_FPGA_CLK3_C_N") (class "Default")
      (node (ref "C217") (pin "2") (pinfunction "2_2") (pintype "passive"))
    )
    (net (code "47") (name "/FLEX_FPGA_CLK3_C_P") (class "Default")
      (node (ref "C216") (pin "2") (pinfunction "2_2") (pintype "passive"))
    )
    (net (code "48") (name "/FLEX_GTP113_CLK0_N") (class "Default")
      (node (ref "IC73") (pin "82") (pinfunction "~{CLK}1~{2}_82") (pintype "bidirectional"))
    )
    (net (code "49") (name "/FLEX_GTP113_CLK0_P") (class "Default")
      (node (ref "IC73") (pin "81") (pinfunction "CLK12_81") (pintype "bidirectional"))
    )
    (net (code "50") (name "/FLEX_GTP113_CLK1_N") (class "Default")
      (node (ref "IC51") (pin "2") (pinfunction "~{Q0}_2") (pintype "output"))
    )
    (net (code "51") (name "/FLEX_GTP113_CLK1_P") (class "Default")
      (node (ref "IC51") (pin "1") (pinfunction "Q0_1") (pintype "output"))
    )
    (net (code "52") (name "/FLEX_GTP116_CLK1_N") (class "Default")
      (node (ref "IC83") (pin "2") (pinfunction "~{Q0}_2") (pintype "output"))
    )
    (net (code "53") (name "/FLEX_GTP116_CLK1_P") (class "Default")
      (node (ref "IC83") (pin "1") (pinfunction "Q0_1") (pintype "output"))
    )
    (net (code "54") (name "/FLEX_GTP213_CLK1_N") (class "Default")
      (node (ref "IC85") (pin "2") (pinfunction "~{Q0}_2") (pintype "output"))
    )
    (net (code "55") (name "/FLEX_GTP213_CLK1_P") (class "Default")
      (node (ref "IC85") (pin "1") (pinfunction "Q0_1") (pintype "output"))
    )
    (net (code "56") (name "/FLEX_GTP216_CLK1_N") (class "Default")
      (node (ref "IC51") (pin "4") (pinfunction "~{Q1}_4") (pintype "output"))
    )
    (net (code "57") (name "/FLEX_GTP216_CLK1_P") (class "Default")
      (node (ref "IC51") (pin "3") (pinfunction "Q1_3") (pintype "output"))
    )
    (net (code "58") (name "/FMC1_1_3_CLK_N") (class "Default")
      (node (ref "IC73") (pin "16") (pinfunction "~{CLK2}_16") (pintype "bidirectional"))
      (node (ref "R296") (pin "2") (pinfunction "2_2") (pintype "passive"))
      (node (ref "R299") (pin "2") (pinfunction "2_2") (pintype "passive"))
    )
    (net (code "59") (name "/FMC1_1_3_CLK_P") (class "Default")
      (node (ref "IC73") (pin "15") (pinfunction "CLK2_15") (pintype "bidirectional"))
      (node (ref "R295") (pin "2") (pinfunction "2_2") (pintype "passive"))
      (node (ref "R443") (pin "2") (pinfunction "2_2") (pintype "passive"))
    )
    (net (code "60") (name "/FMC1_CLK0_M2C_N") (class "Default")
      (node (ref "IC73") (pin "20") (pinfunction "~{CLK3}_20") (pintype "bidirectional"))
    )
    (net (code "61") (name "/FMC1_CLK0_M2C_P") (class "Default")
      (node (ref "IC73") (pin "19") (pinfunction "CLK3_19") (pintype "bidirectional"))
    )
    (net (code "62") (name "/FMC1_CLK1_M2C_N") (class "Default")
      (node (ref "R299") (pin "1") (pinfunction "1_1") (pintype "passive"))
    )
    (net (code "63") (name "/FMC1_CLK1_M2C_P") (class "Default")
      (node (ref "R443") (pin "1") (pinfunction "1_1") (pintype "passive"))
    )
    (net (code "64") (name "/FMC1_CLK2_BIDIR_N") (class "Default")
      (node (ref "IC73") (pin "32") (pinfunction "~{CLK4}_32") (pintype "bidirectional"))
    )
    (net (code "65") (name "/FMC1_CLK2_BIDIR_P") (class "Default")
      (node (ref "IC73") (pin "31") (pinfunction "CLK4_31") (pintype "bidirectional"))
    )
    (net (code "66") (name "/FMC1_CLK3_BIDIR_N") (class "Default")
      (node (ref "R296") (pin "1") (pinfunction "1_1") (pintype "passive"))
    )
    (net (code "67") (name "/FMC1_CLK3_BIDIR_P") (class "Default")
      (node (ref "R295") (pin "1") (pinfunction "1_1") (pintype "passive"))
    )
    (net (code "68") (name "/FMC2_1_3_CLK_N") (class "Default")
      (node (ref "IC73") (pin "11") (pinfunction "~{CLK1}_11") (pintype "bidirectional"))
      (node (ref "R155") (pin "2") (pinfunction "2_2") (pintype "passive"))
      (node (ref "R292") (pin "2") (pinfunction "2_2") (pintype "passive"))
      (node (ref "R568") (pin "2") (pinfunction "2_2") (pintype "passive"))
    )
    (net (code "69") (name "/FMC2_1_3_CLK_P") (class "Default")
      (node (ref "IC73") (pin "10") (pinfunction "CLK1_10") (pintype "bidirectional"))
      (node (ref "R154") (pin "2") (pinfunction "2_2") (pintype "passive"))
      (node (ref "R156") (pin "2") (pinfunction "2_2") (pintype "passive"))
      (node (ref "R567") (pin "2") (pinfunction "2_2") (pintype "passive"))
    )
    (net (code "70") (name "/FMC2_CLK0_M2C_N") (class "Default")
      (node (ref "IC73") (pin "41") (pinfunction "~{CLK6}_41") (pintype "bidirectional"))
    )
    (net (code "71") (name "/FMC2_CLK0_M2C_P") (class "Default")
      (node (ref "IC73") (pin "40") (pinfunction "CLK6_40") (pintype "bidirectional"))
    )
    (net (code "72") (name "/FMC2_CLK1_M2C_N") (class "Default")
      (node (ref "R155") (pin "1") (pinfunction "1_1") (pintype "passive"))
    )
    (net (code "73") (name "/FMC2_CLK1_M2C_P") (class "Default")
      (node (ref "R154") (pin "1") (pinfunction "1_1") (pintype "passive"))
    )
    (net (code "74") (name "/FMC2_CLK2_BIDIR_C_N") (class "Default")
      (node (ref "IC52") (pin "1") (pinfunction "RIN-_1") (pintype "input"))
      (node (ref "R553") (pin "1") (pinfunction "1_1") (pintype "passive"))
      (node (ref "R559") (pin "2") (pinfunction "2_2") (pintype "passive"))
    )
    (net (code "75") (name "/FMC2_CLK2_BIDIR_C_P") (class "Default")
      (node (ref "IC52") (pin "8") (pinfunction "RIN+_8") (pintype "input"))
      (node (ref "R554") (pin "1") (pinfunction "1_1") (pintype "passive"))
      (node (ref "R560") (pin "2") (pinfunction "2_2") (pintype "passive"))
    )
    (net (code "76") (name "/FMC2_CLK2_BIDIR_N") (class "Default")
      (node (ref "IC73") (pin "45") (pinfunction "~{CLK7}_45") (pintype "bidirectional"))
      (node (ref "R553") (pin "2") (pinfunction "2_2") (pintype "passive"))
    )
    (net (code "77") (name "/FMC2_CLK2_BIDIR_P") (class "Default")
      (node (ref "IC73") (pin "44") (pinfunction "CLK7_44") (pintype "bidirectional"))
      (node (ref "R554") (pin "2") (pinfunction "2_2") (pintype "passive"))
    )
    (net (code "78") (name "/FMC2_CLK3_BIDIR_N") (class "Default")
      (node (ref "R292") (pin "1") (pinfunction "1_1") (pintype "passive"))
    )
    (net (code "79") (name "/FMC2_CLK3_BIDIR_P") (class "Default")
      (node (ref "R156") (pin "1") (pinfunction "1_1") (pintype "passive"))
    )
    (net (code "80") (name "/OP15C_C_N") (class "Default")
      (node (ref "IC52") (pin "5") (pinfunction "DOUT-_5") (pintype "output"))
      (node (ref "J11") (pin "1") (pinfunction "1_1") (pintype "bidirectional"))
    )
    (net (code "81") (name "/OP15C_C_P") (class "Default")
      (node (ref "IC52") (pin "6") (pinfunction "DOUT+_6") (pintype "output"))
      (node (ref "J7") (pin "1") (pinfunction "1_1") (pintype "bidirectional"))
    )
    (net (code "82") (name "/P3V3_R0") (class "Default")
      (node (ref "IC73") (pin "52") (pinfunction "S_A1_52") (pintype "input"))
      (node (ref "R141") (pin "1") (pinfunction "1_1") (pintype "passive"))
    )
    (net (code "83") (name "/P3V3_R1") (class "Default")
      (node (ref "IC73") (pin "51") (pinfunction "S_A0_51") (pintype "input"))
      (node (ref "R145") (pin "1") (pinfunction "1_1") (pintype "passive"))
    )
    (net (code "85") (name "/RESETn") (class "Default")
      (node (ref "IC73") (pin "22") (pinfunction "~{MR}_22") (pintype "input"))
    )
    (net (code "86") (name "/RTM_CLK_N") (class "Default")
      (node (ref "R29") (pin "1") (pinfunction "1_1") (pintype "passive"))
    )
    (net (code "87") (name "/RTM_CLK_P") (class "Default")
      (node (ref "R27") (pin "1") (pinfunction "1_1") (pintype "passive"))
    )
    (net (code "88") (name "/RTM_GTP03_N") (class "Default")
      (node (ref "IC83") (pin "4") (pinfunction "~{Q1}_4") (pintype "output"))
    )
    (net (code "89") (name "/RTM_GTP03_P") (class "Default")
      (node (ref "IC83") (pin "3") (pinfunction "Q1_3") (pintype "output"))
    )
    (net (code "90") (name "/RTM_GTP47_N") (class "Default")
      (node (ref "IC85") (pin "4") (pinfunction "~{Q1}_4") (pintype "output"))
    )
    (net (code "91") (name "/RTM_GTP47_P") (class "Default")
      (node (ref "IC85") (pin "3") (pinfunction "Q1_3") (pintype "output"))
    )
    (net (code "92") (name "/RTM_IN_OUT_CLK_N") (class "Default")
      (node (ref "IC73") (pin "7") (pinfunction "~{CLK0}_7") (pintype "bidirectional"))
      (node (ref "R29") (pin "2") (pinfunction "2_2") (pintype "passive"))
      (node (ref "R461") (pin "2") (pinfunction "2_2") (pintype "passive"))
      (node (ref "R566") (pin "2") (pinfunction "2_2") (pintype "passive"))
    )
    (net (code "93") (name "/RTM_IN_OUT_CLK_P") (class "Default")
      (node (ref "IC73") (pin "6") (pinfunction "CLK0_6") (pintype "bidirectional"))
      (node (ref "R27") (pin "2") (pinfunction "2_2") (pintype "passive"))
      (node (ref "R460") (pin "2") (pinfunction "2_2") (pintype "passive"))
      (node (ref "R565") (pin "2") (pinfunction "2_2") (pintype "passive"))
    )
    (net (code "94") (name "/SI57X_PRI_CLK_N") (class "Default")
      (node (ref "IC73") (pin "36") (pinfunction "~{CLK5}_36") (pintype "bidirectional"))
    )
    (net (code "95") (name "/SI57X_PRI_CLK_P") (class "Default")
      (node (ref "IC73") (pin "35") (pinfunction "CLK5_35") (pintype "bidirectional"))
    )
    (net (code "98") (name "/TCLKA_N") (class "Default")
      (node (ref "IC73") (pin "66") (pinfunction "~{CLK}1~{0}_66") (pintype "bidirectional"))
      (node (ref "R550") (pin "1") (pinfunction "1_1") (pintype "passive"))
    )
    (net (code "99") (name "/TCLKA_P") (class "Default")
      (node (ref "IC73") (pin "65") (pinfunction "CLK10_65") (pintype "bidirectional"))
      (node (ref "R542") (pin "1") (pinfunction "1_1") (pintype "passive"))
    )
    (net (code "100") (name "/TCLKB_N") (class "Default")
      (node (ref "IC73") (pin "70") (pinfunction "~{CLK}11_70") (pintype "bidirectional"))
    )
    (net (code "101") (name "/TCLKB_P") (class "Default")
      (node (ref "IC73") (pin "69") (pinfunction "CLK11_69") (pintype "bidirectional"))
    )
    (net (code "102") (name "/TCLKC_N") (class "Default")
      (node (ref "R357") (pin "2") (pinfunction "2_2") (pintype "passive"))
    )
    (net (code "103") (name "/TCLKC_P") (class "Default")
      (node (ref "R356") (pin "2") (pinfunction "2_2") (pintype "passive"))
    )
    (net (code "104") (name "/TCLKD_N") (class "Default")
      (node (ref "R355") (pin "2") (pinfunction "2_2") (pintype "passive"))
    )
    (net (code "105") (name "/TCLKD_P") (class "Default")
      (node (ref "R354") (pin "2") (pinfunction "2_2") (pintype "passive"))
    )
    (net (code "106") (name "/Vbias_CLKSW") (class "Default")
      (node (ref "C616") (pin "2") (pinfunction "2_2") (pintype "passive"))
      (node (ref "C758") (pin "2") (pinfunction "2_2") (pintype "passive"))
      (node (ref "C759") (pin "2") (pinfunction "2_2") (pintype "passive"))
      (node (ref "R557") (pin "2") (pinfunction "2_2") (pintype "passive"))
      (node (ref "R558") (pin "2") (pinfunction "2_2") (pintype "passive"))
      (node (ref "R559") (pin "1") (pinfunction "1_1") (pintype "passive"))
      (node (ref "R560") (pin "1") (pinfunction "1_1") (pintype "passive"))
      (node (ref "R561") (pin "2") (pinfunction "2_2") (pintype "passive"))
      (node (ref "R562") (pin "2") (pinfunction "2_2") (pintype "passive"))
    )
    (net (code "116") (name "GND") (class "Default")
      (node (ref "C211") (pin "1") (pinfunction "1_1") (pintype "passive"))
      (node (ref "C404") (pin "1") (pinfunction "1_1") (pintype "passive"))
      (node (ref "C412") (pin "1") (pinfunction "1_1") (pintype "passive"))
      (node (ref "C414") (pin "1") (pinfunction "1_1") (pintype "passive"))
      (node (ref "C454") (pin "1") (pinfunction "1_1") (pintype "passive"))
      (node (ref "C616") (pin "1") (pinfunction "1_1") (pintype "passive"))
      (node (ref "C758") (pin "1") (pinfunction "1_1") (pintype "passive"))
      (node (ref "C759") (pin "1") (pinfunction "1_1") (pintype "passive"))
      (node (ref "C842") (pin "1") (pinfunction "1_1") (pintype "passive"))
      (node (ref "IC50") (pin "2") (pinfunction "GND_2") (pintype "power_in"))
      (node (ref "IC50") (pin "4") (pinfunction "GND_4") (pintype "output"))
      (node (ref "IC51") (pin "17") (pinfunction "EP_17") (pintype "power_in"))
      (node (ref "IC51") (pin "7") (pinfunction "VEE_7") (pintype "power_in"))
      (node (ref "IC51") (pin "8") (pinfunction "VEE_8") (pintype "power_in"))
      (node (ref "IC52") (pin "2") (pinfunction "GND_2") (pintype "power_in"))
      (node (ref "IC52") (pin "4") (pinfunction "GND_4") (pintype "output"))
      (node (ref "IC73") (pin "101") (pinfunction "EP_101") (pintype "power_in"))
      (node (ref "IC73") (pin "12") (pinfunction "GNDO_CLK1_12") (pintype "power_in"))
      (node (ref "IC73") (pin "17") (pinfunction "GNDO_CLK2_17") (pintype "power_in"))
      (node (ref "IC73") (pin "2") (pinfunction "GND_2") (pintype "power_in"))
      (node (ref "IC73") (pin "21") (pinfunction "GNDO_CLK3_21") (pintype "power_in"))
      (node (ref "IC73") (pin "24") (pinfunction "GND_24") (pintype "power_in"))
      (node (ref "IC73") (pin "29") (pinfunction "GND_DIGITAL_29") (pintype "power_in"))
      (node (ref "IC73") (pin "3") (pinfunction "GND_3") (pintype "power_in"))
      (node (ref "IC73") (pin "33") (pinfunction "GNDO_CLK4_33") (pintype "power_in"))
      (node (ref "IC73") (pin "37") (pinfunction "GNDO_CLK5_37") (pintype "power_in"))
      (node (ref "IC73") (pin "42") (pinfunction "GNDO_CLK6_42") (pintype "power_in"))
      (node (ref "IC73") (pin "46") (pinfunction "GNDO_CLK7_46") (pintype "power_in"))
      (node (ref "IC73") (pin "47") (pinfunction "GND_S_47") (pintype "power_in"))
      (node (ref "IC73") (pin "48") (pinfunction "GND_48") (pintype "power_in"))
      (node (ref "IC73") (pin "54") (pinfunction "GND_DIGITAL_54") (pintype "power_in"))
      (node (ref "IC73") (pin "58") (pinfunction "GNDO_CLK8_58") (pintype "power_in"))
      (node (ref "IC73") (pin "62") (pinfunction "GNDO_CLK9_62") (pintype "power_in"))
      (node (ref "IC73") (pin "67") (pinfunction "GNDO_CLK10_67") (pintype "power_in"))
      (node (ref "IC73") (pin "71") (pinfunction "GNDO_CLK11_71") (pintype "power_in"))
      (node (ref "IC73") (pin "72") (pinfunction "GND_S_72") (pintype "power_in"))
      (node (ref "IC73") (pin "73") (pinfunction "GND_73") (pintype "power_in"))
      (node (ref "IC73") (pin "77") (pinfunction "GND_77") (pintype "power_in"))
      (node (ref "IC73") (pin "78") (pinfunction "GND_S_78") (pintype "power_in"))
      (node (ref "IC73") (pin "8") (pinfunction "GNDO_CLK0_8") (pintype "power_in"))
      (node (ref "IC73") (pin "83") (pinfunction "GNDO_CLK12_83") (pintype "power_in"))
      (node (ref "IC73") (pin "87") (pinfunction "GNDO_CLK13_87") (pintype "power_in"))
      (node (ref "IC73") (pin "92") (pinfunction "GNDO_CLK14_92") (pintype "power_in"))
      (node (ref "IC73") (pin "96") (pinfunction "GNDO_CLK15_96") (pintype "power_in"))
      (node (ref "IC73") (pin "99") (pinfunction "GND_S_99") (pintype "power_in"))
      (node (ref "IC83") (pin "17") (pinfunction "EP_17") (pintype "power_in"))
      (node (ref "IC83") (pin "7") (pinfunction "VEE_7") (pintype "power_in"))
      (node (ref "IC83") (pin "8") (pinfunction "VEE_8") (pintype "power_in"))
      (node (ref "IC85") (pin "17") (pinfunction "EP_17") (pintype "power_in"))
      (node (ref "IC85") (pin "7") (pinfunction "VEE_7") (pintype "power_in"))
      (node (ref "IC85") (pin "8") (pinfunction "VEE_8") (pintype "power_in"))
      (node (ref "J11") (pin "2") (pinfunction "2_2") (pintype "bidirectional"))
      (node (ref "J7") (pin "2") (pinfunction "2_2") (pintype "bidirectional"))
      (node (ref "R562") (pin "1") (pinfunction "1_1") (pintype "passive"))
    )
    (net (code "117") (name "MUX1_VDD") (class "Default")
      (node (ref "IC73") (pin "1") (pinfunction "VDD_1") (pintype "power_in"))
      (node (ref "IC73") (pin "100") (pinfunction "VDD_100") (pintype "power_in"))
      (node (ref "IC73") (pin "4") (pinfunction "VDD_4") (pintype "power_in"))
      (node (ref "IC73") (pin "50") (pinfunction "VDD_50") (pintype "power_in"))
      (node (ref "IC73") (pin "74") (pinfunction "VDD_74") (pintype "power_in"))
      (node (ref "IC73") (pin "75") (pinfunction "VDD_75") (pintype "power_in"))
      (node (ref "IC73") (pin "76") (pinfunction "VDD_76") (pintype "power_in"))
      (node (ref "IC73") (pin "98") (pinfunction "VDD_98") (pintype "power_in"))
      (node (ref "R141") (pin "2") (pinfunction "2_2") (pintype "passive"))
      (node (ref "R145") (pin "2") (pinfunction "2_2") (pintype "passive"))
    )
    (net (code "118") (name "MUX1_VDD_CLK00") (class "Default")
      (node (ref "IC73") (pin "5") (pinfunction "VDDO_CLK0_5") (pintype "power_in"))
    )
    (net (code "119") (name "MUX1_VDD_CLK01") (class "Default")
      (node (ref "IC73") (pin "9") (pinfunction "VDDO_CLK1_9") (pintype "power_in"))
    )
    (net (code "120") (name "MUX1_VDD_CLK02") (class "Default")
      (node (ref "IC73") (pin "14") (pinfunction "VDDO_CLK2_14") (pintype "power_in"))
    )
    (net (code "121") (name "MUX1_VDD_CLK03") (class "Default")
      (node (ref "IC73") (pin "18") (pinfunction "VDDO_CLK3_18") (pintype "power_in"))
    )
    (net (code "122") (name "MUX1_VDD_CLK04") (class "Default")
      (node (ref "IC73") (pin "30") (pinfunction "VDDO_CLK4_30") (pintype "power_in"))
    )
    (net (code "123") (name "MUX1_VDD_CLK05") (class "Default")
      (node (ref "IC73") (pin "34") (pinfunction "VDDO_CLK5_34") (pintype "power_in"))
    )
    (net (code "124") (name "MUX1_VDD_CLK06") (class "Default")
      (node (ref "IC73") (pin "39") (pinfunction "VDDO_CLK6_39") (pintype "power_in"))
    )
    (net (code "125") (name "MUX1_VDD_CLK07") (class "Default")
      (node (ref "IC73") (pin "43") (pinfunction "VDDO_CLK7_43") (pintype "power_in"))
    )
    (net (code "126") (name "MUX1_VDD_CLK08") (class "Default")
      (node (ref "IC73") (pin "55") (pinfunction "VDDO_CLK8_55") (pintype "power_in"))
    )
    (net (code "127") (name "MUX1_VDD_CLK09") (class "Default")
      (node (ref "IC73") (pin "59") (pinfunction "VDDO_CLK9_59") (pintype "power_in"))
    )
    (net (code "128") (name "MUX1_VDD_CLK10") (class "Default")
      (node (ref "IC73") (pin "64") (pinfunction "VDDO_CLK10_64") (pintype "power_in"))
    )
    (net (code "129") (name "MUX1_VDD_CLK11") (class "Default")
      (node (ref "IC73") (pin "68") (pinfunction "VDDO_CLK11_68") (pintype "power_in"))
    )
    (net (code "130") (name "MUX1_VDD_CLK12") (class "Default")
      (node (ref "IC73") (pin "80") (pinfunction "VDDO_CLK12_80") (pintype "power_in"))
    )
    (net (code "131") (name "MUX1_VDD_CLK13") (class "Default")
      (node (ref "IC73") (pin "84") (pinfunction "VDDO_CLK13_84") (pintype "power_in"))
    )
    (net (code "132") (name "MUX1_VDD_CLK14") (class "Default")
      (node (ref "IC73") (pin "89") (pinfunction "VDDO_CLK14_89") (pintype "power_in"))
    )
    (net (code "133") (name "MUX1_VDD_CLK15") (class "Default")
      (node (ref "IC73") (pin "93") (pinfunction "VDDO_CLK15_93") (pintype "power_in"))
    )
    (net (code "134") (name "MUX1_VDD_DIG") (class "Default")
      (node (ref "IC73") (pin "23") (pinfunction "VDD_DIGITAL_23") (pintype "power_in"))
      (node (ref "IC73") (pin "28") (pinfunction "VDD_DIGITAL_28") (pintype "power_in"))
      (node (ref "IC73") (pin "53") (pinfunction "VDD_DIGITAL_53") (pintype "power_in"))
    )
    (net (code "135") (name "Net-(IC51-VTD)") (class "Default")
      (node (ref "IC51") (pin "12") (pinfunction "VTD_12") (pintype "passive"))
      (node (ref "R151") (pin "2") (pinfunction "2_2") (pintype "passive"))
    )
    (net (code "136") (name "Net-(IC51-~{VTD})") (class "Default")
      (node (ref "IC51") (pin "9") (pinfunction "~{VTD}_9") (pintype "passive"))
      (node (ref "R157") (pin "2") (pinfunction "2_2") (pintype "passive"))
    )
    (net (code "137") (name "Net-(IC83-VTD)") (class "Default")
      (node (ref "IC83") (pin "12") (pinfunction "VTD_12") (pintype "passive"))
      (node (ref "R444") (pin "2") (pinfunction "2_2") (pintype "passive"))
    )
    (net (code "138") (name "Net-(IC83-~{VTD})") (class "Default")
      (node (ref "IC83") (pin "9") (pinfunction "~{VTD}_9") (pintype "passive"))
      (node (ref "R447") (pin "2") (pinfunction "2_2") (pintype "passive"))
    )
    (net (code "139") (name "Net-(IC85-VTD)") (class "Default")
      (node (ref "IC85") (pin "12") (pinfunction "VTD_12") (pintype "passive"))
      (node (ref "R451") (pin "2") (pinfunction "2_2") (pintype "passive"))
    )
    (net (code "140") (name "Net-(IC85-~{VTD})") (class "Default")
      (node (ref "IC85") (pin "9") (pinfunction "~{VTD}_9") (pintype "passive"))
      (node (ref "R452") (pin "2") (pinfunction "2_2") (pintype "passive"))
    )
    (net (code "141") (name "Net-(R151-Pad1)") (class "Default")
      (node (ref "R151") (pin "1") (pinfunction "1_1") (pintype "passive"))
      (node (ref "R157") (pin "1") (pinfunction "1_1") (pintype "passive"))
    )
    (net (code "142") (name "Net-(R444-Pad1)") (class "Default")
      (node (ref "R444") (pin "1") (pinfunction "1_1") (pintype "passive"))
      (node (ref "R447") (pin "1") (pinfunction "1_1") (pintype "passive"))
    )
    (net (code "143") (name "Net-(R451-Pad1)") (class "Default")
      (node (ref "R451") (pin "1") (pinfunction "1_1") (pintype "passive"))
      (node (ref "R452") (pin "1") (pinfunction "1_1") (pintype "passive"))
    )
    (net (code "144") (name "P3V3") (class "Default")
      (node (ref "L11") (pin "1") (pinfunction "1_1") (pintype "passive"))
    )
    (net (code "145") (name "P3V3_CLKSW") (class "Default")
      (node (ref "C211") (pin "2") (pinfunction "2_2") (pintype "passive"))
      (node (ref "C404") (pin "2") (pinfunction "2_2") (pintype "passive"))
      (node (ref "C412") (pin "2") (pinfunction "2_2") (pintype "passive"))
      (node (ref "C414") (pin "2") (pinfunction "2_2") (pintype "passive"))
      (node (ref "C454") (pin "2") (pinfunction "2_2") (pintype "passive"))
      (node (ref "C842") (pin "2") (pinfunction "2_2") (pintype "passive"))
      (node (ref "IC50") (pin "3") (pinfunction "EN_3") (pintype "input"))
      (node (ref "IC50") (pin "7") (pinfunction "VCC_7") (pintype "power_in"))
      (node (ref "IC51") (pin "13") (pinfunction "VCC_13") (pintype "power_in"))
      (node (ref "IC51") (pin "14") (pinfunction "VCC_14") (pintype "power_in"))
      (node (ref "IC51") (pin "15") (pinfunction "VCC_15") (pintype "power_in"))
      (node (ref "IC51") (pin "16") (pinfunction "VCC_16") (pintype "power_in"))
      (node (ref "IC51") (pin "5") (pinfunction "VCC_5") (pintype "power_in"))
      (node (ref "IC52") (pin "3") (pinfunction "EN_3") (pintype "input"))
      (node (ref "IC52") (pin "7") (pinfunction "VCC_7") (pintype "power_in"))
      (node (ref "IC83") (pin "13") (pinfunction "VCC_13") (pintype "power_in"))
      (node (ref "IC83") (pin "14") (pinfunction "VCC_14") (pintype "power_in"))
      (node (ref "IC83") (pin "15") (pinfunction "VCC_15") (pintype "power_in"))
      (node (ref "IC83") (pin "16") (pinfunction "VCC_16") (pintype "power_in"))
      (node (ref "IC83") (pin "5") (pinfunction "VCC_5") (pintype "power_in"))
      (node (ref "IC85") (pin "13") (pinfunction "VCC_13") (pintype "power_in"))
      (node (ref "IC85") (pin "14") (pinfunction "VCC_14") (pintype "power_in"))
      (node (ref "IC85") (pin "15") (pinfunction "VCC_15") (pintype "power_in"))
      (node (ref "IC85") (pin "16") (pinfunction "VCC_16") (pintype "power_in"))
      (node (ref "IC85") (pin "5") (pinfunction "VCC_5") (pintype "power_in"))
      (node (ref "L11") (pin "2") (pinfunction "2_2") (pintype "passive"))
      (node (ref "R561") (pin "1") (pinfunction "1_1") (pintype "passive"))
    )
    (net (code "146") (name "unconnected-(IC51-NC-Pad6)") (class "Default")
      (node (ref "IC51") (pin "6") (pinfunction "NC_6") (pintype "passive"))
    )
    (net (code "147") (name "unconnected-(IC73-NC-Pad13)") (class "Default")
      (node (ref "IC73") (pin "13") (pinfunction "NC_13") (pintype "passive"))
    )
    (net (code "148") (name "unconnected-(IC73-NC-Pad27)") (class "Default")
      (node (ref "IC73") (pin "27") (pinfunction "NC_27") (pintype "passive"))
    )
    (net (code "149") (name "unconnected-(IC73-NC-Pad38)") (class "Default")
      (node (ref "IC73") (pin "38") (pinfunction "NC_38") (pintype "passive"))
    )
    (net (code "150") (name "unconnected-(IC73-NC-Pad49)") (class "Default")
      (node (ref "IC73") (pin "49") (pinfunction "NC_49") (pintype "passive"))
    )
    (net (code "151") (name "unconnected-(IC73-NC-Pad63)") (class "Default")
      (node (ref "IC73") (pin "63") (pinfunction "NC_63") (pintype "passive"))
    )
    (net (code "152") (name "unconnected-(IC73-NC-Pad79)") (class "Default")
      (node (ref "IC73") (pin "79") (pinfunction "NC_79") (pintype "passive"))
    )
    (net (code "153") (name "unconnected-(IC73-NC-Pad88)") (class "Default")
      (node (ref "IC73") (pin "88") (pinfunction "NC_88") (pintype "passive"))
    )
    (net (code "154") (name "unconnected-(IC73-NC-Pad97)") (class "Default")
      (node (ref "IC73") (pin "97") (pinfunction "NC_97") (pintype "passive"))
    )
    (net (code "155") (name "unconnected-(IC83-NC-Pad6)") (class "Default")
      (node (ref "IC83") (pin "6") (pinfunction "NC_6") (pintype "passive"))
    )
    (net (code "156") (name "unconnected-(IC85-NC-Pad6)") (class "Default")
      (node (ref "IC85") (pin "6") (pinfunction "NC_6") (pintype "passive"))
    )
  )
)
